# ENGI301_Project-2.net
KiCad netlist of a schematic drawn in EAGLE
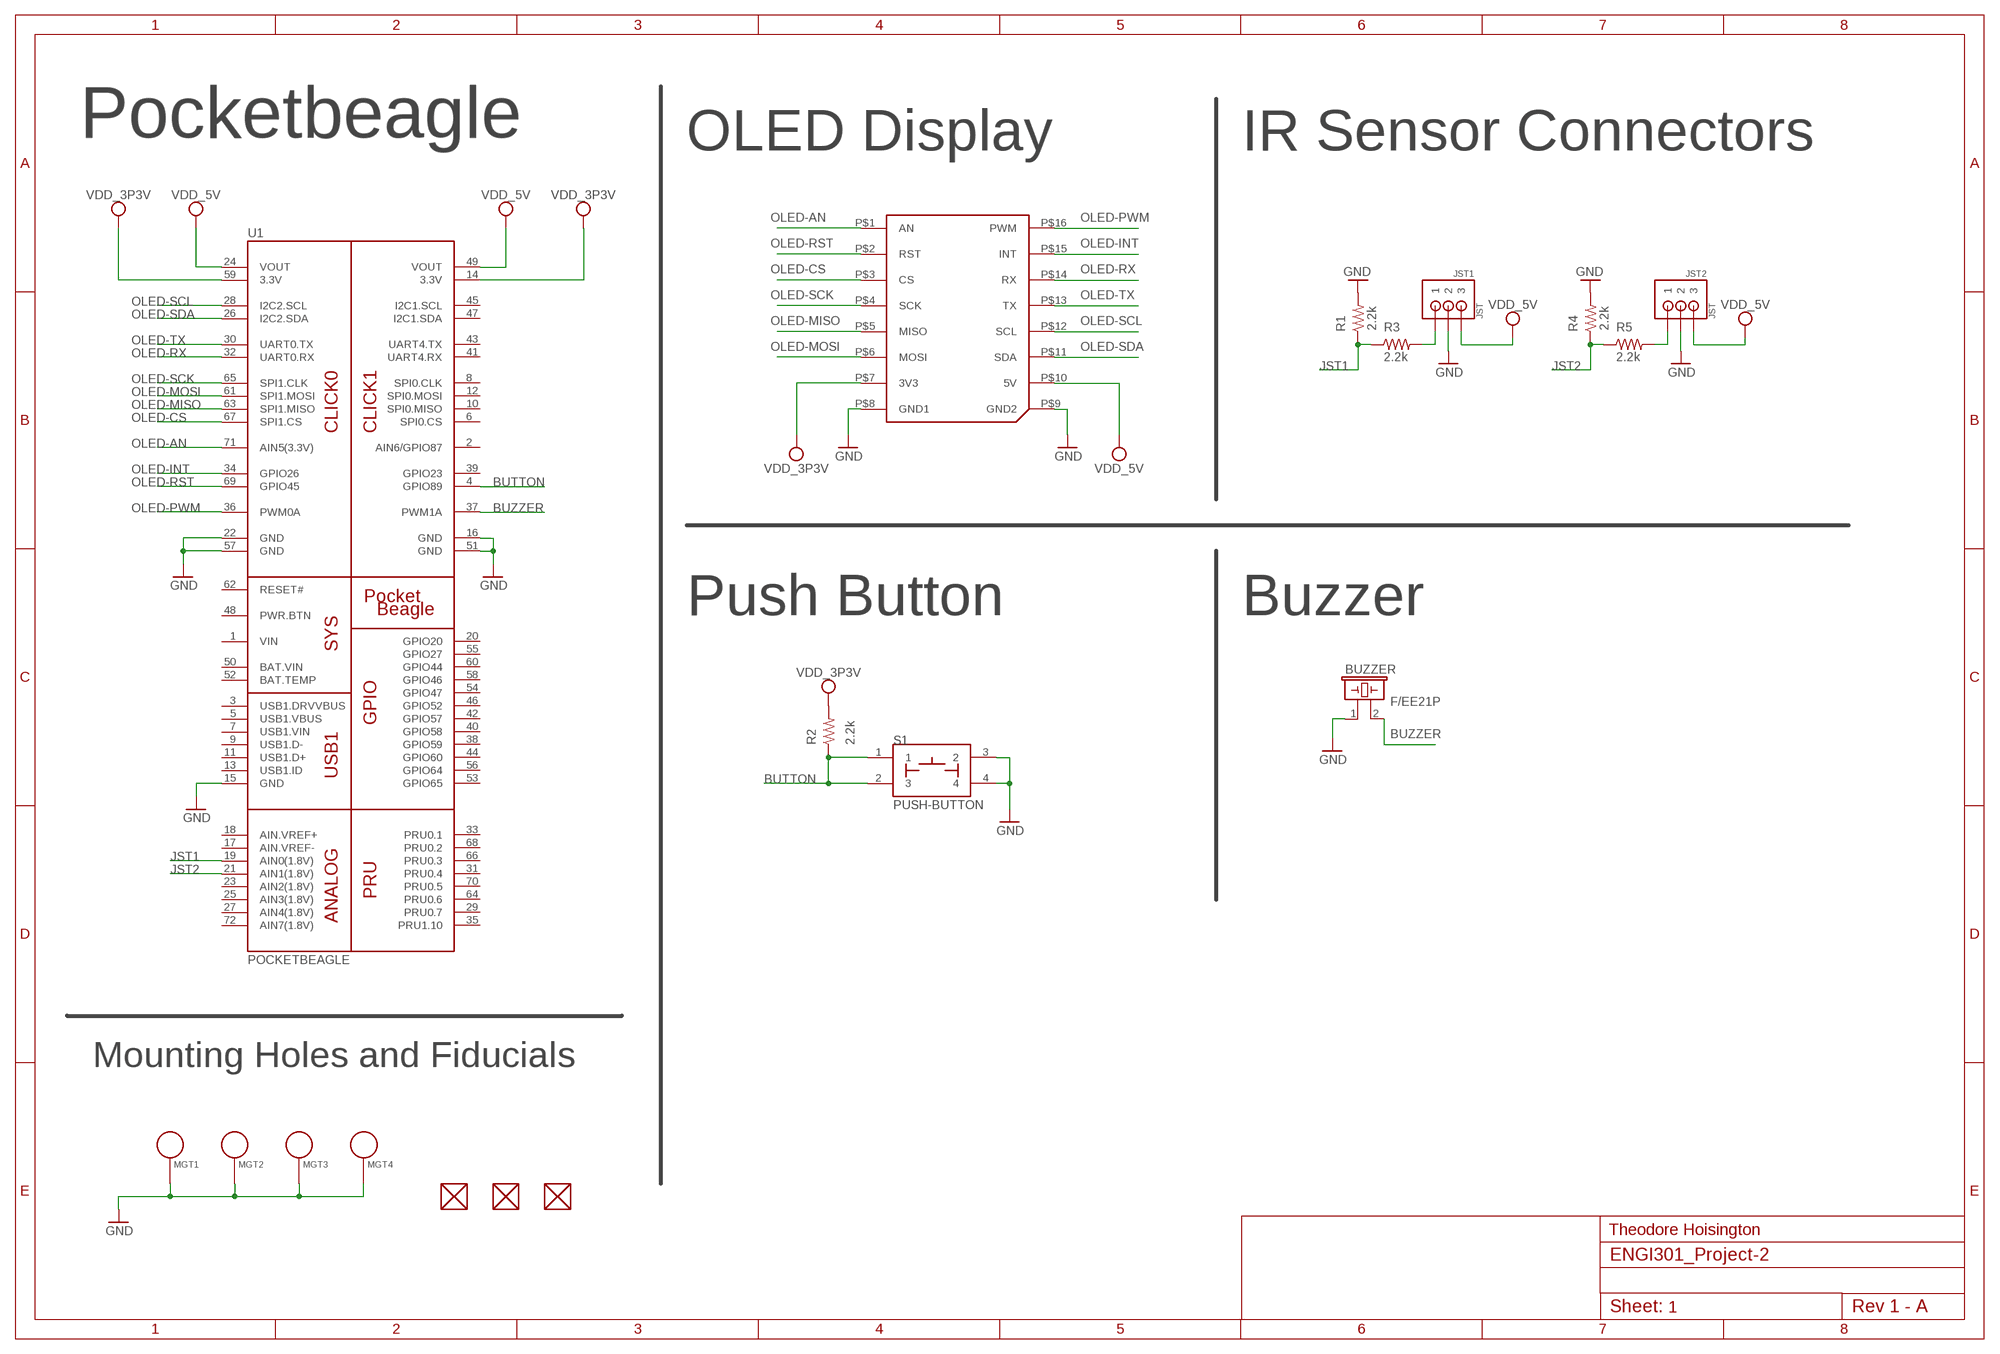
[diagram p0: schematic, sheet 1]

(export (version "E")
  (design (tool "Eeschema 10.0.6"))
  (components
    (comp (ref "BUZZER")
      (value "F/EE21P")
      (footprint "eagle-import:F_EE21P")
      (libsource (lib "eagle-import") (part "F/EE21P"))
    )
    (comp (ref "FUD1")
      (value "FIDUCIAL")
      (footprint "eagle-import:FIDUCIAL_40MIL")
      (libsource (lib "eagle-import") (part "FIDUCIAL"))
    )
    (comp (ref "FUD2")
      (value "FIDUCIAL")
      (footprint "eagle-import:FIDUCIAL_40MIL")
      (libsource (lib "eagle-import") (part "FIDUCIAL"))
    )
    (comp (ref "FUD3")
      (value "FIDUCIAL")
      (footprint "eagle-import:FIDUCIAL_40MIL")
      (libsource (lib "eagle-import") (part "FIDUCIAL"))
    )
    (comp (ref "JST1")
      (value "JST")
      (footprint "eagle-import:JST_HEADER")
      (libsource (lib "eagle-import") (part "JST"))
    )
    (comp (ref "JST2")
      (value "JST")
      (footprint "eagle-import:JST_HEADER")
      (libsource (lib "eagle-import") (part "JST"))
    )
    (comp (ref "MGT1")
      (value "MOUNTING_HOLE")
      (footprint "eagle-import:MOUNTING_HOLE")
      (libsource (lib "eagle-import") (part "MOUNTING_HOLE"))
    )
    (comp (ref "MGT2")
      (value "MOUNTING_HOLE")
      (footprint "eagle-import:MOUNTING_HOLE")
      (libsource (lib "eagle-import") (part "MOUNTING_HOLE"))
    )
    (comp (ref "MGT3")
      (value "MOUNTING_HOLE")
      (footprint "eagle-import:MOUNTING_HOLE")
      (libsource (lib "eagle-import") (part "MOUNTING_HOLE"))
    )
    (comp (ref "MGT4")
      (value "MOUNTING_HOLE")
      (footprint "eagle-import:MOUNTING_HOLE")
      (libsource (lib "eagle-import") (part "MOUNTING_HOLE"))
    )
    (comp (ref "R1")
      (value "2.2k")
      (footprint "eagle-import:R0603")
      (libsource (lib "eagle-import") (part "R_R0603"))
    )
    (comp (ref "R2")
      (value "2.2k")
      (footprint "eagle-import:R0603")
      (libsource (lib "eagle-import") (part "R_R0603"))
    )
    (comp (ref "R3")
      (value "2.2k")
      (footprint "eagle-import:R0603")
      (libsource (lib "eagle-import") (part "R_R0603"))
    )
    (comp (ref "R4")
      (value "2.2k")
      (footprint "eagle-import:R0603")
      (libsource (lib "eagle-import") (part "R_R0603"))
    )
    (comp (ref "R5")
      (value "2.2k")
      (footprint "eagle-import:R0603")
      (libsource (lib "eagle-import") (part "R_R0603"))
    )
    (comp (ref "S1")
      (value "PUSH-BUTTON")
      (footprint "eagle-import:BUTTON_12.5MM")
      (libsource (lib "eagle-import") (part "PUSH-BUTTON"))
    )
    (comp (ref "U1")
      (value "POCKETBEAGLE")
      (footprint "eagle-import:POCKETBEAGLE")
      (libsource (lib "eagle-import") (part "POCKETBEAGLE"))
    )
    (comp (ref "U2")
      (value "MIKROE_CLICKLARGE")
      (footprint "eagle-import:MIKROE_BUS_LARGE")
      (libsource (lib "eagle-import") (part "MIKROE_CLICKLARGE"))
    )
  )
  (nets
    (net (code "1") (name "/BAT.VIN") (class "Default")
      (node (ref "U1") (pin "50") (pinfunction "BAT.VIN_50") (pintype "power_in"))
    )
    (net (code "2") (name "/BUTTON") (class "Default")
      (node (ref "R2") (pin "1") (pinfunction "1_1") (pintype "passive"))
      (node (ref "S1") (pin "1") (pinfunction "1_1") (pintype "bidirectional"))
      (node (ref "S1") (pin "2") (pinfunction "3_2") (pintype "bidirectional"))
      (node (ref "U1") (pin "4") (pinfunction "GPIO89_4") (pintype "bidirectional"))
    )
    (net (code "3") (name "/BUZZER") (class "Default")
      (node (ref "BUZZER") (pin "2") (pinfunction "2_2") (pintype "passive"))
      (node (ref "U1") (pin "37") (pinfunction "PWM1A_37") (pintype "bidirectional"))
    )
    (net (code "4") (name "/JST1") (class "Default")
      (node (ref "R1") (pin "1") (pinfunction "1_1") (pintype "passive"))
      (node (ref "R3") (pin "1") (pinfunction "1_1") (pintype "passive"))
      (node (ref "U1") (pin "19") (pinfunction "AIN0(1.8V)_19") (pintype "input"))
    )
    (net (code "5") (name "/JST2") (class "Default")
      (node (ref "R4") (pin "1") (pinfunction "1_1") (pintype "passive"))
      (node (ref "R5") (pin "1") (pinfunction "1_1") (pintype "passive"))
      (node (ref "U1") (pin "21") (pinfunction "AIN1(1.8V)_21") (pintype "input"))
    )
    (net (code "6") (name "/OLED-AN") (class "Default")
      (node (ref "U1") (pin "71") (pinfunction "AIN5(3.3V)_71") (pintype "bidirectional"))
      (node (ref "U2") (pin "P$1") (pinfunction "AN_P$1") (pintype "bidirectional"))
    )
    (net (code "7") (name "/OLED-CS") (class "Default")
      (node (ref "U1") (pin "67") (pinfunction "SPI1.CS_67") (pintype "bidirectional"))
      (node (ref "U2") (pin "P$3") (pinfunction "CS_P$3") (pintype "bidirectional"))
    )
    (net (code "8") (name "/OLED-INT") (class "Default")
      (node (ref "U1") (pin "34") (pinfunction "GPIO26_34") (pintype "bidirectional"))
      (node (ref "U2") (pin "P$15") (pinfunction "INT_P$15") (pintype "bidirectional"))
    )
    (net (code "9") (name "/OLED-MISO") (class "Default")
      (node (ref "U1") (pin "63") (pinfunction "SPI1.MISO_63") (pintype "bidirectional"))
      (node (ref "U2") (pin "P$5") (pinfunction "MISO_P$5") (pintype "bidirectional"))
    )
    (net (code "10") (name "/OLED-MOSI") (class "Default")
      (node (ref "U1") (pin "61") (pinfunction "SPI1.MOSI_61") (pintype "bidirectional"))
      (node (ref "U2") (pin "P$6") (pinfunction "MOSI_P$6") (pintype "bidirectional"))
    )
    (net (code "11") (name "/OLED-PWM") (class "Default")
      (node (ref "U1") (pin "36") (pinfunction "PWM0A_36") (pintype "bidirectional"))
      (node (ref "U2") (pin "P$16") (pinfunction "PWM_P$16") (pintype "bidirectional"))
    )
    (net (code "12") (name "/OLED-RST") (class "Default")
      (node (ref "U1") (pin "69") (pinfunction "GPIO45_69") (pintype "bidirectional"))
      (node (ref "U2") (pin "P$2") (pinfunction "RST_P$2") (pintype "bidirectional"))
    )
    (net (code "13") (name "/OLED-RX") (class "Default")
      (node (ref "U1") (pin "32") (pinfunction "UART0.RX_32") (pintype "bidirectional"))
      (node (ref "U2") (pin "P$14") (pinfunction "RX_P$14") (pintype "bidirectional"))
    )
    (net (code "14") (name "/OLED-SCK") (class "Default")
      (node (ref "U1") (pin "65") (pinfunction "SPI1.CLK_65") (pintype "bidirectional"))
      (node (ref "U2") (pin "P$4") (pinfunction "SCK_P$4") (pintype "bidirectional"))
    )
    (net (code "15") (name "/OLED-SCL") (class "Default")
      (node (ref "U1") (pin "28") (pinfunction "I2C2.SCL_28") (pintype "bidirectional"))
      (node (ref "U2") (pin "P$12") (pinfunction "SCL_P$12") (pintype "bidirectional"))
    )
    (net (code "16") (name "/OLED-SDA") (class "Default")
      (node (ref "U1") (pin "26") (pinfunction "I2C2.SDA_26") (pintype "bidirectional"))
      (node (ref "U2") (pin "P$11") (pinfunction "SDA_P$11") (pintype "bidirectional"))
    )
    (net (code "17") (name "/OLED-TX") (class "Default")
      (node (ref "U1") (pin "30") (pinfunction "UART0.TX_30") (pintype "bidirectional"))
      (node (ref "U2") (pin "P$13") (pinfunction "TX_P$13") (pintype "bidirectional"))
    )
    (net (code "18") (name "/VIN") (class "Default")
      (node (ref "U1") (pin "1") (pinfunction "VIN_1") (pintype "power_in"))
    )
    (net (code "19") (name "GND") (class "Default")
      (node (ref "BUZZER") (pin "1") (pinfunction "1_1") (pintype "passive"))
      (node (ref "JST1") (pin "P2") (pinfunction "2_P2") (pintype "bidirectional"))
      (node (ref "JST2") (pin "P2") (pinfunction "2_P2") (pintype "bidirectional"))
      (node (ref "MGT1") (pin "P$1") (pinfunction "P$1_P$1") (pintype "bidirectional"))
      (node (ref "MGT2") (pin "P$1") (pinfunction "P$1_P$1") (pintype "bidirectional"))
      (node (ref "MGT3") (pin "P$1") (pinfunction "P$1_P$1") (pintype "bidirectional"))
      (node (ref "MGT4") (pin "P$1") (pinfunction "P$1_P$1") (pintype "bidirectional"))
      (node (ref "R1") (pin "2") (pinfunction "2_2") (pintype "passive"))
      (node (ref "R4") (pin "2") (pinfunction "2_2") (pintype "passive"))
      (node (ref "S1") (pin "3") (pinfunction "2_3") (pintype "bidirectional"))
      (node (ref "S1") (pin "4") (pinfunction "4_4") (pintype "bidirectional"))
      (node (ref "U1") (pin "15") (pinfunction "GND_15") (pintype "bidirectional"))
      (node (ref "U1") (pin "16") (pinfunction "GND_16") (pintype "power_in"))
      (node (ref "U1") (pin "22") (pinfunction "GND_22") (pintype "power_in"))
      (node (ref "U1") (pin "51") (pinfunction "GND_51") (pintype "power_in"))
      (node (ref "U1") (pin "57") (pinfunction "GND_57") (pintype "power_in"))
      (node (ref "U2") (pin "P$8") (pinfunction "GND1_P$8") (pintype "bidirectional"))
      (node (ref "U2") (pin "P$9") (pinfunction "GND2_P$9") (pintype "bidirectional"))
    )
    (net (code "20") (name "Net-(JST1-1)") (class "Default")
      (node (ref "JST1") (pin "P3") (pinfunction "1_P3") (pintype "bidirectional"))
      (node (ref "R3") (pin "2") (pinfunction "2_2") (pintype "passive"))
    )
    (net (code "21") (name "Net-(JST2-1)") (class "Default")
      (node (ref "JST2") (pin "P3") (pinfunction "1_P3") (pintype "bidirectional"))
      (node (ref "R5") (pin "2") (pinfunction "2_2") (pintype "passive"))
    )
    (net (code "22") (name "VDD_3P3V") (class "Default")
      (node (ref "R2") (pin "2") (pinfunction "2_2") (pintype "passive"))
      (node (ref "U1") (pin "14") (pinfunction "3.3V_14") (pintype "power_in"))
      (node (ref "U1") (pin "59") (pinfunction "3.3V_59") (pintype "power_in"))
      (node (ref "U2") (pin "P$7") (pinfunction "3V3_P$7") (pintype "bidirectional"))
    )
    (net (code "23") (name "VDD_5V") (class "Default")
      (node (ref "JST1") (pin "P1") (pinfunction "3_P1") (pintype "bidirectional"))
      (node (ref "JST2") (pin "P1") (pinfunction "3_P1") (pintype "bidirectional"))
      (node (ref "U1") (pin "24") (pinfunction "VOUT_24") (pintype "power_in"))
      (node (ref "U1") (pin "49") (pinfunction "VOUT_49") (pintype "power_in"))
      (node (ref "U2") (pin "P$10") (pinfunction "5V_P$10") (pintype "bidirectional"))
    )
    (net (code "24") (name "unconnected-(FUD1-PadP$1)") (class "Default")
      (node (ref "FUD1") (pin "P$1") (pinfunction "P$1_P$1") (pintype "no_connect"))
    )
    (net (code "25") (name "unconnected-(FUD2-PadP$1)") (class "Default")
      (node (ref "FUD2") (pin "P$1") (pinfunction "P$1_P$1") (pintype "no_connect"))
    )
    (net (code "26") (name "unconnected-(FUD3-PadP$1)") (class "Default")
      (node (ref "FUD3") (pin "P$1") (pinfunction "P$1_P$1") (pintype "no_connect"))
    )
    (net (code "27") (name "unconnected-(U1-AIN.VREF+-Pad18)") (class "Default")
      (node (ref "U1") (pin "18") (pinfunction "AIN.VREF+_18") (pintype "input"))
    )
    (net (code "28") (name "unconnected-(U1-AIN.VREF--Pad17)") (class "Default")
      (node (ref "U1") (pin "17") (pinfunction "AIN.VREF-_17") (pintype "input"))
    )
    (net (code "29") (name "unconnected-(U1-AIN2(1.8V)-Pad23)") (class "Default")
      (node (ref "U1") (pin "23") (pinfunction "AIN2(1.8V)_23") (pintype "input"))
    )
    (net (code "30") (name "unconnected-(U1-AIN3(1.8V)-Pad25)") (class "Default")
      (node (ref "U1") (pin "25") (pinfunction "AIN3(1.8V)_25") (pintype "input"))
    )
    (net (code "31") (name "unconnected-(U1-AIN4(1.8V)-Pad27)") (class "Default")
      (node (ref "U1") (pin "27") (pinfunction "AIN4(1.8V)_27") (pintype "input"))
    )
    (net (code "32") (name "unconnected-(U1-AIN6{slash}GPIO87-Pad2)") (class "Default")
      (node (ref "U1") (pin "2") (pinfunction "AIN6/GPIO87_2") (pintype "bidirectional"))
    )
    (net (code "33") (name "unconnected-(U1-AIN7(1.8V)-Pad72)") (class "Default")
      (node (ref "U1") (pin "72") (pinfunction "AIN7(1.8V)_72") (pintype "input"))
    )
    (net (code "34") (name "unconnected-(U1-BAT.TEMP-Pad52)") (class "Default")
      (node (ref "U1") (pin "52") (pinfunction "BAT.TEMP_52") (pintype "input"))
    )
    (net (code "35") (name "unconnected-(U1-GPIO20-Pad20)") (class "Default")
      (node (ref "U1") (pin "20") (pinfunction "GPIO20_20") (pintype "bidirectional"))
    )
    (net (code "36") (name "unconnected-(U1-GPIO23-Pad39)") (class "Default")
      (node (ref "U1") (pin "39") (pinfunction "GPIO23_39") (pintype "bidirectional"))
    )
    (net (code "37") (name "unconnected-(U1-GPIO27-Pad55)") (class "Default")
      (node (ref "U1") (pin "55") (pinfunction "GPIO27_55") (pintype "bidirectional"))
    )
    (net (code "38") (name "unconnected-(U1-GPIO44-Pad60)") (class "Default")
      (node (ref "U1") (pin "60") (pinfunction "GPIO44_60") (pintype "bidirectional"))
    )
    (net (code "39") (name "unconnected-(U1-GPIO46-Pad58)") (class "Default")
      (node (ref "U1") (pin "58") (pinfunction "GPIO46_58") (pintype "bidirectional"))
    )
    (net (code "40") (name "unconnected-(U1-GPIO47-Pad54)") (class "Default")
      (node (ref "U1") (pin "54") (pinfunction "GPIO47_54") (pintype "bidirectional"))
    )
    (net (code "41") (name "unconnected-(U1-GPIO52-Pad46)") (class "Default")
      (node (ref "U1") (pin "46") (pinfunction "GPIO52_46") (pintype "bidirectional"))
    )
    (net (code "42") (name "unconnected-(U1-GPIO57-Pad42)") (class "Default")
      (node (ref "U1") (pin "42") (pinfunction "GPIO57_42") (pintype "bidirectional"))
    )
    (net (code "43") (name "unconnected-(U1-GPIO58-Pad40)") (class "Default")
      (node (ref "U1") (pin "40") (pinfunction "GPIO58_40") (pintype "bidirectional"))
    )
    (net (code "44") (name "unconnected-(U1-GPIO59-Pad38)") (class "Default")
      (node (ref "U1") (pin "38") (pinfunction "GPIO59_38") (pintype "bidirectional"))
    )
    (net (code "45") (name "unconnected-(U1-GPIO60-Pad44)") (class "Default")
      (node (ref "U1") (pin "44") (pinfunction "GPIO60_44") (pintype "bidirectional"))
    )
    (net (code "46") (name "unconnected-(U1-GPIO64-Pad56)") (class "Default")
      (node (ref "U1") (pin "56") (pinfunction "GPIO64_56") (pintype "bidirectional"))
    )
    (net (code "47") (name "unconnected-(U1-GPIO65-Pad53)") (class "Default")
      (node (ref "U1") (pin "53") (pinfunction "GPIO65_53") (pintype "bidirectional"))
    )
    (net (code "48") (name "unconnected-(U1-I2C1.SCL-Pad45)") (class "Default")
      (node (ref "U1") (pin "45") (pinfunction "I2C1.SCL_45") (pintype "bidirectional"))
    )
    (net (code "49") (name "unconnected-(U1-I2C1.SDA-Pad47)") (class "Default")
      (node (ref "U1") (pin "47") (pinfunction "I2C1.SDA_47") (pintype "bidirectional"))
    )
    (net (code "50") (name "unconnected-(U1-PRU0.1-Pad33)") (class "Default")
      (node (ref "U1") (pin "33") (pinfunction "PRU0.1_33") (pintype "bidirectional"))
    )
    (net (code "51") (name "unconnected-(U1-PRU0.2-Pad68)") (class "Default")
      (node (ref "U1") (pin "68") (pinfunction "PRU0.2_68") (pintype "bidirectional"))
    )
    (net (code "52") (name "unconnected-(U1-PRU0.3-Pad66)") (class "Default")
      (node (ref "U1") (pin "66") (pinfunction "PRU0.3_66") (pintype "bidirectional"))
    )
    (net (code "53") (name "unconnected-(U1-PRU0.4-Pad31)") (class "Default")
      (node (ref "U1") (pin "31") (pinfunction "PRU0.4_31") (pintype "bidirectional"))
    )
    (net (code "54") (name "unconnected-(U1-PRU0.5-Pad70)") (class "Default")
      (node (ref "U1") (pin "70") (pinfunction "PRU0.5_70") (pintype "bidirectional"))
    )
    (net (code "55") (name "unconnected-(U1-PRU0.6-Pad64)") (class "Default")
      (node (ref "U1") (pin "64") (pinfunction "PRU0.6_64") (pintype "bidirectional"))
    )
    (net (code "56") (name "unconnected-(U1-PRU0.7-Pad29)") (class "Default")
      (node (ref "U1") (pin "29") (pinfunction "PRU0.7_29") (pintype "bidirectional"))
    )
    (net (code "57") (name "unconnected-(U1-PRU1.10-Pad35)") (class "Default")
      (node (ref "U1") (pin "35") (pinfunction "PRU1.10_35") (pintype "bidirectional"))
    )
    (net (code "58") (name "unconnected-(U1-PWR.BTN-Pad48)") (class "Default")
      (node (ref "U1") (pin "48") (pinfunction "PWR.BTN_48") (pintype "input"))
    )
    (net (code "59") (name "unconnected-(U1-RESET#-Pad62)") (class "Default")
      (node (ref "U1") (pin "62") (pinfunction "RESET#_62") (pintype "input"))
    )
    (net (code "60") (name "unconnected-(U1-SPI0.CLK-Pad8)") (class "Default")
      (node (ref "U1") (pin "8") (pinfunction "SPI0.CLK_8") (pintype "bidirectional"))
    )
    (net (code "61") (name "unconnected-(U1-SPI0.CS-Pad6)") (class "Default")
      (node (ref "U1") (pin "6") (pinfunction "SPI0.CS_6") (pintype "bidirectional"))
    )
    (net (code "62") (name "unconnected-(U1-SPI0.MISO-Pad10)") (class "Default")
      (node (ref "U1") (pin "10") (pinfunction "SPI0.MISO_10") (pintype "bidirectional"))
    )
    (net (code "63") (name "unconnected-(U1-SPI0.MOSI-Pad12)") (class "Default")
      (node (ref "U1") (pin "12") (pinfunction "SPI0.MOSI_12") (pintype "bidirectional"))
    )
    (net (code "64") (name "unconnected-(U1-UART4.RX-Pad41)") (class "Default")
      (node (ref "U1") (pin "41") (pinfunction "UART4.RX_41") (pintype "bidirectional"))
    )
    (net (code "65") (name "unconnected-(U1-UART4.TX-Pad43)") (class "Default")
      (node (ref "U1") (pin "43") (pinfunction "UART4.TX_43") (pintype "bidirectional"))
    )
    (net (code "66") (name "unconnected-(U1-USB1.D+-Pad11)") (class "Default")
      (node (ref "U1") (pin "11") (pinfunction "USB1.D+_11") (pintype "bidirectional"))
    )
    (net (code "67") (name "unconnected-(U1-USB1.D--Pad9)") (class "Default")
      (node (ref "U1") (pin "9") (pinfunction "USB1.D-_9") (pintype "bidirectional"))
    )
    (net (code "68") (name "unconnected-(U1-USB1.DRVVBUS-Pad3)") (class "Default")
      (node (ref "U1") (pin "3") (pinfunction "USB1.DRVVBUS_3") (pintype "bidirectional"))
    )
    (net (code "69") (name "unconnected-(U1-USB1.ID-Pad13)") (class "Default")
      (node (ref "U1") (pin "13") (pinfunction "USB1.ID_13") (pintype "bidirectional"))
    )
    (net (code "70") (name "unconnected-(U1-USB1.VBUS-Pad5)") (class "Default")
      (node (ref "U1") (pin "5") (pinfunction "USB1.VBUS_5") (pintype "bidirectional"))
    )
    (net (code "71") (name "unconnected-(U1-USB1.VIN-Pad7)") (class "Default")
      (node (ref "U1") (pin "7") (pinfunction "USB1.VIN_7") (pintype "bidirectional"))
    )
  )
)
